# F4_Fc_Board.net
KiCad netlist of a schematic drawn in Altium Designer
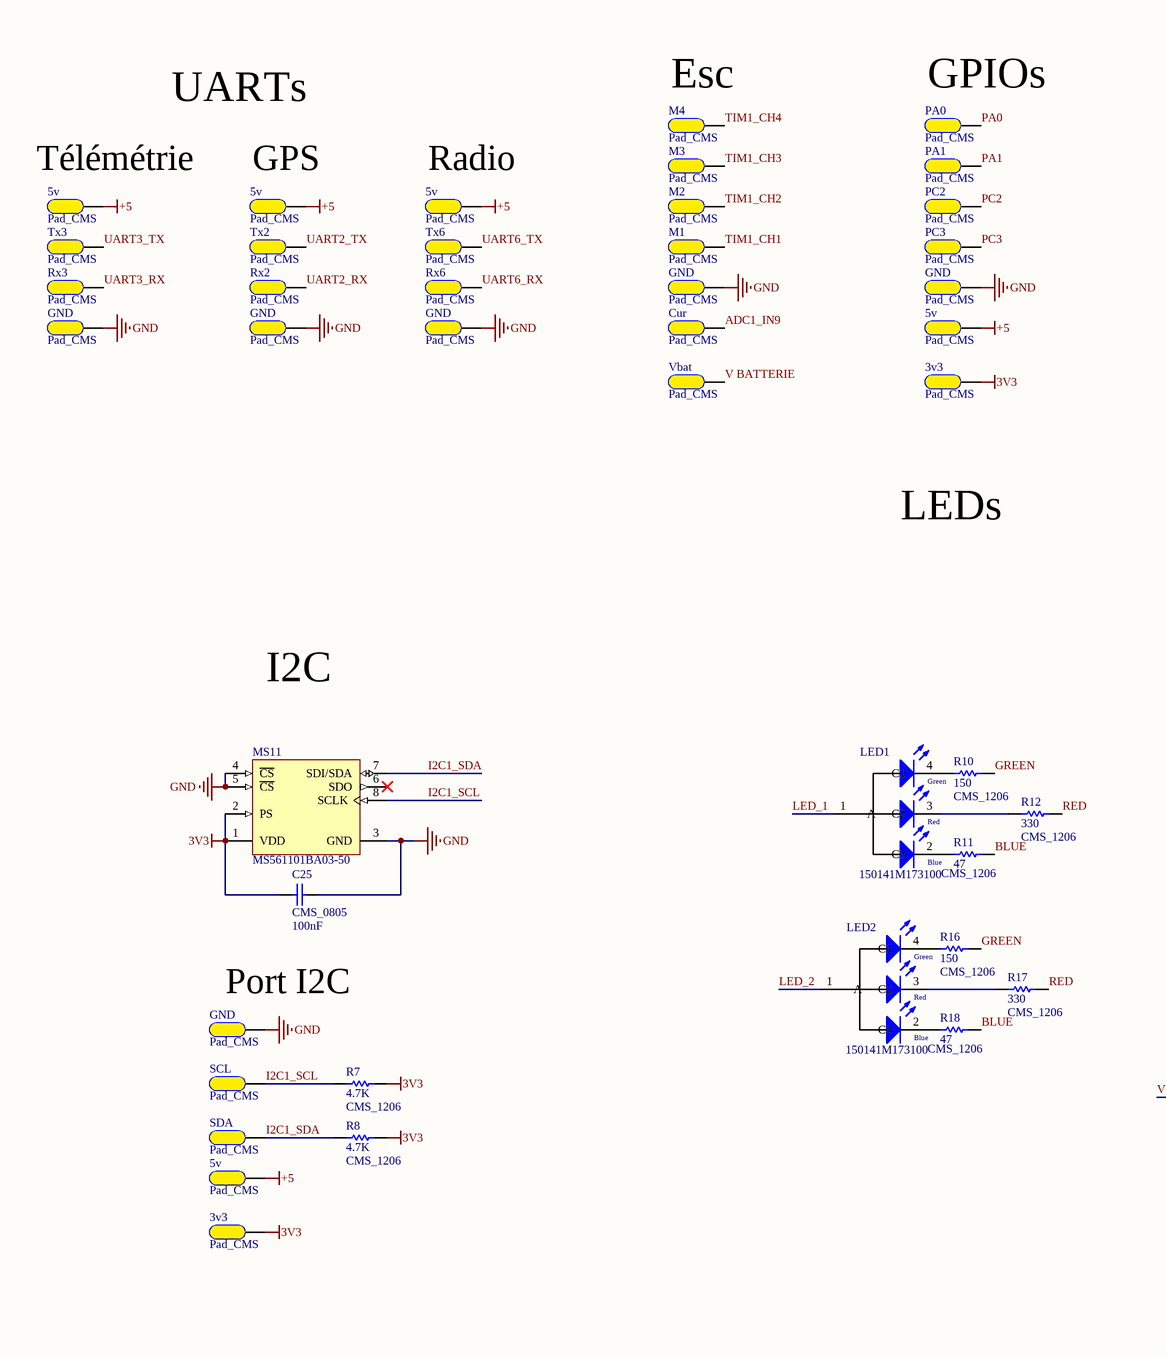
[diagram p0: F4_Fc_Board.SchDoc, left]
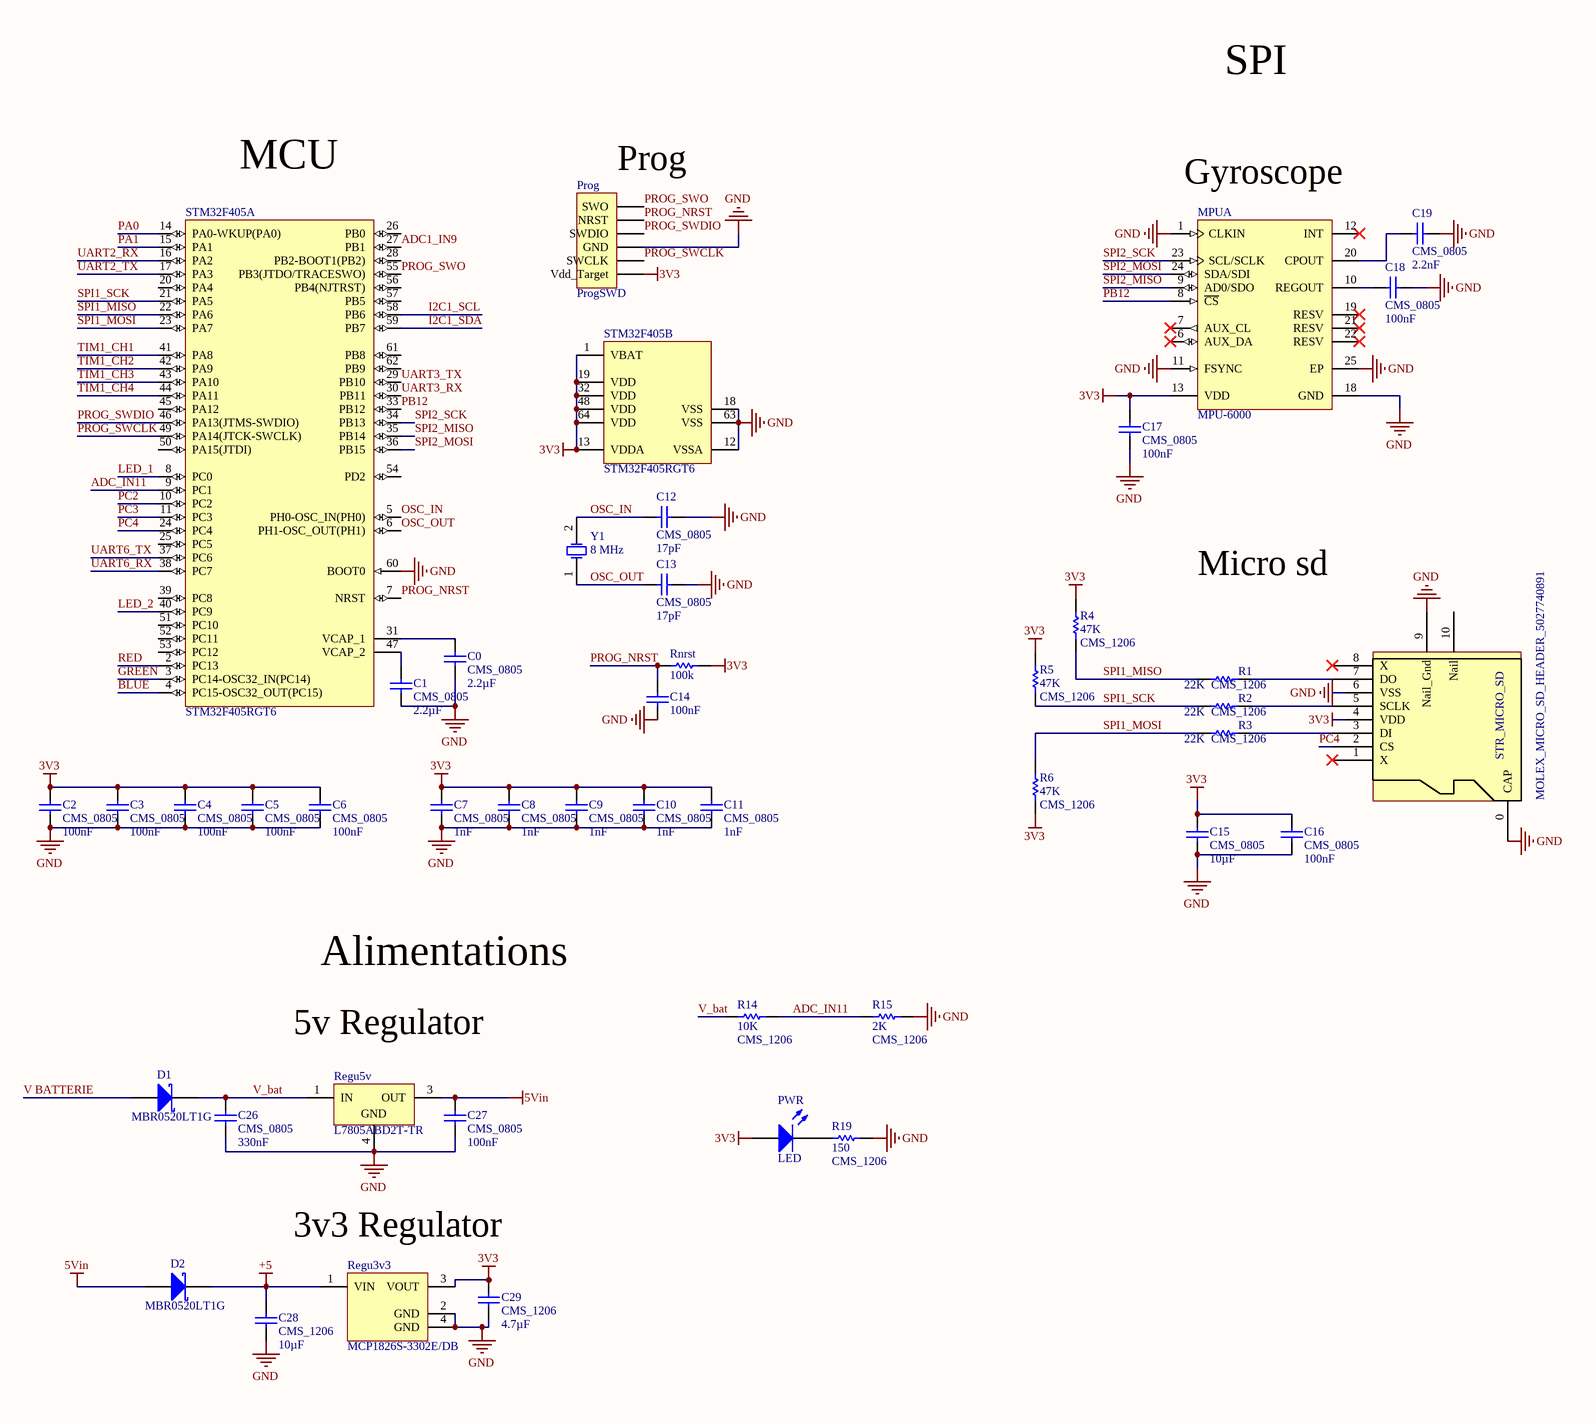
[diagram p1: F4_Fc_Board.SchDoc, right]

(export (version "E")
  (design (tool "Eeschema 10.0.6"))
  (components
    (comp (ref "3v3")
      (value "Pad_CMS")
      (footprint "PAD_CMS_5.08x2.54")
      (description "Pad pour souder un fil")
      (fields (field (name "PUBLISHER") "Damien Guitton"))
      (libsource (lib "Connecteur") (part "Pad_CMS"))
    )
    (comp (ref "5v")
      (value "Pad_CMS")
      (footprint "PAD_CMS_5.08x2.54")
      (description "Pad pour souder un fil")
      (fields (field (name "PUBLISHER") "Damien Guitton"))
      (libsource (lib "Connecteur") (part "Pad_CMS"))
    )
    (comp (ref "C0")
      (value "2.2µF")
      (footprint "CONDENSATEUR_CMS_0805")
      (description "CONDENSATEUR CMS CERAMIQUE 0805")
      (fields (field (name "TYPE") "CMS_0805") (field (name "Comment") "CMS_0805"))
      (libsource (lib "composants passifs") (part "CONDENSATEUR_CMS_CER_0805"))
    )
    (comp (ref "C1")
      (value "2.2µF")
      (footprint "CONDENSATEUR_CMS_0805")
      (description "CONDENSATEUR CMS CERAMIQUE 0805")
      (fields (field (name "TYPE") "CMS_0805") (field (name "Comment") "CMS_0805"))
      (libsource (lib "composants passifs") (part "CONDENSATEUR_CMS_CER_0805"))
    )
    (comp (ref "C2")
      (value "100nF")
      (footprint "CONDENSATEUR_CMS_0805")
      (description "CONDENSATEUR CMS CERAMIQUE 0805")
      (fields (field (name "TYPE") "CMS_0805") (field (name "Comment") "CMS_0805"))
      (libsource (lib "composants passifs") (part "CONDENSATEUR_CMS_CER_0805"))
    )
    (comp (ref "C3")
      (value "100nF")
      (footprint "CONDENSATEUR_CMS_0805")
      (description "CONDENSATEUR CMS CERAMIQUE 0805")
      (fields (field (name "TYPE") "CMS_0805") (field (name "Comment") "CMS_0805"))
      (libsource (lib "composants passifs") (part "CONDENSATEUR_CMS_CER_0805"))
    )
    (comp (ref "C4")
      (value "100nF")
      (footprint "CONDENSATEUR_CMS_0805")
      (description "CONDENSATEUR CMS CERAMIQUE 0805")
      (fields (field (name "TYPE") "CMS_0805") (field (name "Comment") "CMS_0805"))
      (libsource (lib "composants passifs") (part "CONDENSATEUR_CMS_CER_0805"))
    )
    (comp (ref "C5")
      (value "100nF")
      (footprint "CONDENSATEUR_CMS_0805")
      (description "CONDENSATEUR CMS CERAMIQUE 0805")
      (fields (field (name "TYPE") "CMS_0805") (field (name "Comment") "CMS_0805"))
      (libsource (lib "composants passifs") (part "CONDENSATEUR_CMS_CER_0805"))
    )
    (comp (ref "C6")
      (value "100nF")
      (footprint "CONDENSATEUR_CMS_0805")
      (description "CONDENSATEUR CMS CERAMIQUE 0805")
      (fields (field (name "TYPE") "CMS_0805") (field (name "Comment") "CMS_0805"))
      (libsource (lib "composants passifs") (part "CONDENSATEUR_CMS_CER_0805"))
    )
    (comp (ref "C7")
      (value "1nF")
      (footprint "CONDENSATEUR_CMS_0805")
      (description "CONDENSATEUR CMS CERAMIQUE 0805")
      (fields (field (name "TYPE") "CMS_0805") (field (name "Comment") "CMS_0805"))
      (libsource (lib "composants passifs") (part "CONDENSATEUR_CMS_CER_0805"))
    )
    (comp (ref "C8")
      (value "1nF")
      (footprint "CONDENSATEUR_CMS_0805")
      (description "CONDENSATEUR CMS CERAMIQUE 0805")
      (fields (field (name "TYPE") "CMS_0805") (field (name "Comment") "CMS_0805"))
      (libsource (lib "composants passifs") (part "CONDENSATEUR_CMS_CER_0805"))
    )
    (comp (ref "C9")
      (value "1nF")
      (footprint "CONDENSATEUR_CMS_0805")
      (description "CONDENSATEUR CMS CERAMIQUE 0805")
      (fields (field (name "TYPE") "CMS_0805") (field (name "Comment") "CMS_0805"))
      (libsource (lib "composants passifs") (part "CONDENSATEUR_CMS_CER_0805"))
    )
    (comp (ref "C10")
      (value "1nF")
      (footprint "CONDENSATEUR_CMS_0805")
      (description "CONDENSATEUR CMS CERAMIQUE 0805")
      (fields (field (name "TYPE") "CMS_0805") (field (name "Comment") "CMS_0805"))
      (libsource (lib "composants passifs") (part "CONDENSATEUR_CMS_CER_0805"))
    )
    (comp (ref "C11")
      (value "1nF")
      (footprint "CONDENSATEUR_CMS_0805")
      (description "CONDENSATEUR CMS CERAMIQUE 0805")
      (fields (field (name "TYPE") "CMS_0805") (field (name "Comment") "CMS_0805"))
      (libsource (lib "composants passifs") (part "CONDENSATEUR_CMS_CER_0805"))
    )
    (comp (ref "C12")
      (value "17pF")
      (footprint "CONDENSATEUR_CMS_0805")
      (description "CONDENSATEUR CMS CERAMIQUE 0805")
      (fields (field (name "TYPE") "CMS_0805") (field (name "Comment") "CMS_0805"))
      (libsource (lib "composants passifs") (part "CONDENSATEUR_CMS_CER_0805"))
    )
    (comp (ref "C13")
      (value "17pF")
      (footprint "CONDENSATEUR_CMS_0805")
      (description "CONDENSATEUR CMS CERAMIQUE 0805")
      (fields (field (name "TYPE") "CMS_0805") (field (name "Comment") "CMS_0805"))
      (libsource (lib "composants passifs") (part "CONDENSATEUR_CMS_CER_0805"))
    )
    (comp (ref "C14")
      (value "100nF")
      (footprint "C0805_N")
      (description "Capacitor")
      (fields (field (name "PUBLISHER") "Altium Limited"))
      (libsource (lib "_ROBOT") (part "Condensateur"))
    )
    (comp (ref "C15")
      (value "10µF")
      (footprint "CONDENSATEUR_CMS_0805")
      (description "CONDENSATEUR CMS CERAMIQUE 0805")
      (fields (field (name "TYPE") "CMS_0805") (field (name "Comment") "CMS_0805"))
      (libsource (lib "composants passifs") (part "CONDENSATEUR_CMS_CER_0805"))
    )
    (comp (ref "C16")
      (value "100nF")
      (footprint "CONDENSATEUR_CMS_0805")
      (description "CONDENSATEUR CMS CERAMIQUE 0805")
      (fields (field (name "TYPE") "CMS_0805") (field (name "Comment") "CMS_0805"))
      (libsource (lib "composants passifs") (part "CONDENSATEUR_CMS_CER_0805"))
    )
    (comp (ref "C17")
      (value "100nF")
      (footprint "CONDENSATEUR_CMS_0805")
      (description "CONDENSATEUR CMS CERAMIQUE 0805")
      (fields (field (name "TYPE") "CMS_0805") (field (name "Comment") "CMS_0805"))
      (libsource (lib "composants passifs") (part "CONDENSATEUR_CMS_CER_0805"))
    )
    (comp (ref "C18")
      (value "100nF")
      (footprint "CONDENSATEUR_CMS_0805")
      (description "CONDENSATEUR CMS CERAMIQUE 0805")
      (fields (field (name "TYPE") "CMS_0805") (field (name "Comment") "CMS_0805"))
      (libsource (lib "composants passifs") (part "CONDENSATEUR_CMS_CER_0805"))
    )
    (comp (ref "C19")
      (value "2.2nF")
      (footprint "CONDENSATEUR_CMS_0805")
      (description "CONDENSATEUR CMS CERAMIQUE 0805")
      (fields (field (name "TYPE") "CMS_0805") (field (name "Comment") "CMS_0805"))
      (libsource (lib "composants passifs") (part "CONDENSATEUR_CMS_CER_0805"))
    )
    (comp (ref "C25")
      (value "100nF")
      (footprint "CONDENSATEUR_CMS_0805")
      (description "CONDENSATEUR CMS CERAMIQUE 0805")
      (fields (field (name "TYPE") "CMS_0805") (field (name "Comment") "CMS_0805"))
      (libsource (lib "composants passifs") (part "CONDENSATEUR_CMS_CER_0805"))
    )
    (comp (ref "C26")
      (value "330nF")
      (footprint "CONDENSATEUR_CMS_0805")
      (description "CONDENSATEUR CMS CERAMIQUE 0805")
      (fields (field (name "TYPE") "CMS_0805") (field (name "Comment") "CMS_0805"))
      (libsource (lib "composants passifs") (part "CONDENSATEUR_CMS_CER_0805"))
    )
    (comp (ref "C27")
      (value "100nF")
      (footprint "CONDENSATEUR_CMS_0805")
      (description "CONDENSATEUR CMS CERAMIQUE 0805")
      (fields (field (name "TYPE") "CMS_0805") (field (name "Comment") "CMS_0805"))
      (libsource (lib "composants passifs") (part "CONDENSATEUR_CMS_CER_0805"))
    )
    (comp (ref "C28")
      (value "10µF")
      (footprint "CONDENSATEUR_CMS_1206")
      (description "CONDENSATEUR CMS CERAMIQUE 1206")
      (fields (field (name "TYPE") "CMS_1206") (field (name "Comment") "CMS_1206"))
      (libsource (lib "composants passifs") (part "CONDENSATEUR_CMS_CER_1206"))
    )
    (comp (ref "C29")
      (value "4.7µF")
      (footprint "CONDENSATEUR_CMS_1206")
      (description "CONDENSATEUR CMS CERAMIQUE 1206")
      (fields (field (name "TYPE") "CMS_1206") (field (name "Comment") "CMS_1206"))
      (libsource (lib "composants passifs") (part "CONDENSATEUR_CMS_CER_1206"))
    )
    (comp (ref "Cur")
      (value "Pad_CMS")
      (footprint "PAD_CMS_5.08x2.54")
      (description "Pad pour souder un fil")
      (fields (field (name "PUBLISHER") "Damien Guitton"))
      (libsource (lib "Connecteur") (part "Pad_CMS"))
    )
    (comp (ref "D1")
      (value "MBR0520LT1G")
      (footprint "ONSC-SOD-123-2-425-04_V")
      (description "Schottky Power Rectifier, 20 V, 5.5 A, -65 to 125 degC, 2-Pin SMD, RoHS, Tape and Reel")
      (fields (field (name "MANUFACTURER") "ON Semiconductor"))
      (libsource (lib "ESEO (Ecole Supérieure d'Electronique de l'Ouest)") (part "DSKY-AK-2"))
    )
    (comp (ref "D2")
      (value "MBR0520LT1G")
      (footprint "ONSC-SOD-123-2-425-04_V")
      (description "Schottky Power Rectifier, 20 V, 5.5 A, -65 to 125 degC, 2-Pin SMD, RoHS, Tape and Reel")
      (fields (field (name "MANUFACTURER") "ON Semiconductor"))
      (libsource (lib "ESEO (Ecole Supérieure d'Electronique de l'Ouest)") (part "DSKY-AK-2"))
    )
    (comp (ref "GND")
      (value "Pad_CMS")
      (footprint "PAD_CMS_5.08x2.54")
      (description "Pad pour souder un fil")
      (fields (field (name "PUBLISHER") "Damien Guitton"))
      (libsource (lib "Connecteur") (part "Pad_CMS"))
    )
    (comp (ref "LED1")
      (value "150141M173100")
      (footprint "3528_A")
      (description "SMD Full-Color Top LED, WL-SFTW, Red & Green & Blue")
      (fields (field (name "MANUFACTURER") "Wuerth Elektronik"))
      (libsource (lib "Altium Content Vault") (part "WE-LED_RGB_A1B2R3G4-4"))
    )
    (comp (ref "LED2")
      (value "150141M173100")
      (footprint "3528_A")
      (description "SMD Full-Color Top LED, WL-SFTW, Red & Green & Blue")
      (fields (field (name "MANUFACTURER") "Wuerth Elektronik"))
      (libsource (lib "Altium Content Vault") (part "WE-LED_RGB_A1B2R3G4-4"))
    )
    (comp (ref "M1")
      (value "Pad_CMS")
      (footprint "PAD_CMS_5.08x2.54")
      (description "Pad pour souder un fil")
      (fields (field (name "PUBLISHER") "Damien Guitton"))
      (libsource (lib "Connecteur") (part "Pad_CMS"))
    )
    (comp (ref "M2")
      (value "Pad_CMS")
      (footprint "PAD_CMS_5.08x2.54")
      (description "Pad pour souder un fil")
      (fields (field (name "PUBLISHER") "Damien Guitton"))
      (libsource (lib "Connecteur") (part "Pad_CMS"))
    )
    (comp (ref "M3")
      (value "Pad_CMS")
      (footprint "PAD_CMS_5.08x2.54")
      (description "Pad pour souder un fil")
      (fields (field (name "PUBLISHER") "Damien Guitton"))
      (libsource (lib "Connecteur") (part "Pad_CMS"))
    )
    (comp (ref "M4")
      (value "Pad_CMS")
      (footprint "PAD_CMS_5.08x2.54")
      (description "Pad pour souder un fil")
      (fields (field (name "PUBLISHER") "Damien Guitton"))
      (libsource (lib "Connecteur") (part "Pad_CMS"))
    )
    (comp (ref "MPU")
      (value "MPU-6000")
      (footprint "INSE-QFN-24_V")
      (fields (field (name "MANUFACTURER") "InvenSense"))
      (libsource (lib "Altium Content Vault") (part "INSE-MPU-6000"))
    )
    (comp (ref "MS11")
      (value "MS561101BA03-50")
      (footprint "MSI-MS561101BA03-50-8_V")
      (fields (field (name "MANUFACTURER") "Measurement Specialties"))
      (libsource (lib "Altium Content Vault") (part "MSI-MS561101BA03-50-8"))
    )
    (comp (ref "PA0")
      (value "Pad_CMS")
      (footprint "PAD_CMS_5.08x2.54")
      (description "Pad pour souder un fil")
      (fields (field (name "PUBLISHER") "Damien Guitton"))
      (libsource (lib "Connecteur") (part "Pad_CMS"))
    )
    (comp (ref "PA1")
      (value "Pad_CMS")
      (footprint "PAD_CMS_5.08x2.54")
      (description "Pad pour souder un fil")
      (fields (field (name "PUBLISHER") "Damien Guitton"))
      (libsource (lib "Connecteur") (part "Pad_CMS"))
    )
    (comp (ref "PC2")
      (value "Pad_CMS")
      (footprint "PAD_CMS_5.08x2.54")
      (description "Pad pour souder un fil")
      (fields (field (name "PUBLISHER") "Damien Guitton"))
      (libsource (lib "Connecteur") (part "Pad_CMS"))
    )
    (comp (ref "PC3")
      (value "Pad_CMS")
      (footprint "PAD_CMS_5.08x2.54")
      (description "Pad pour souder un fil")
      (fields (field (name "PUBLISHER") "Damien Guitton"))
      (libsource (lib "Connecteur") (part "Pad_CMS"))
    )
    (comp (ref "Prog")
      (value "ProgSWD")
      (footprint "HDR1X6")
      (description "Header, 6-Pin")
      (fields (field (name "PUBLISHER") "Altium Limited"))
      (libsource (lib "DG_Connecteur") (part "Header 6"))
    )
    (comp (ref "PWR")
      (value "LED")
      (footprint "LED_1206")
      (description "Typical LED")
      (fields (field (name "PUBLISHER") "Altium Limited"))
      (libsource (lib "_ROBOT") (part "LED"))
    )
    (comp (ref "R1")
      (value "22K")
      (footprint "RESISTANCE_CMS_1206")
      (description "RESISTANCE CMS 1206")
      (fields (field (name "TYPE") "CMS_1206") (field (name "Comment") "RESISTANCE_CMS_1206"))
      (libsource (lib "composants passifs") (part "RESISTANCE_CMS_1206"))
    )
    (comp (ref "R2")
      (value "22K")
      (footprint "RESISTANCE_CMS_1206")
      (description "RESISTANCE CMS 1206")
      (fields (field (name "TYPE") "CMS_1206") (field (name "Comment") "RESISTANCE_CMS_1206"))
      (libsource (lib "composants passifs") (part "RESISTANCE_CMS_1206"))
    )
    (comp (ref "R3")
      (value "22K")
      (footprint "RESISTANCE_CMS_1206")
      (description "RESISTANCE CMS 1206")
      (fields (field (name "TYPE") "CMS_1206") (field (name "Comment") "RESISTANCE_CMS_1206"))
      (libsource (lib "composants passifs") (part "RESISTANCE_CMS_1206"))
    )
    (comp (ref "R4")
      (value "47K")
      (footprint "RESISTANCE_CMS_1206")
      (description "RESISTANCE CMS 1206")
      (fields (field (name "TYPE") "CMS_1206") (field (name "Comment") "RESISTANCE_CMS_1206"))
      (libsource (lib "composants passifs") (part "RESISTANCE_CMS_1206"))
    )
    (comp (ref "R5")
      (value "47K")
      (footprint "RESISTANCE_CMS_1206")
      (description "RESISTANCE CMS 1206")
      (fields (field (name "TYPE") "CMS_1206") (field (name "Comment") "RESISTANCE_CMS_1206"))
      (libsource (lib "composants passifs") (part "RESISTANCE_CMS_1206"))
    )
    (comp (ref "R6")
      (value "47K")
      (footprint "RESISTANCE_CMS_1206")
      (description "RESISTANCE CMS 1206")
      (fields (field (name "TYPE") "CMS_1206") (field (name "Comment") "RESISTANCE_CMS_1206"))
      (libsource (lib "composants passifs") (part "RESISTANCE_CMS_1206"))
    )
    (comp (ref "R7")
      (value "4.7K")
      (footprint "RESISTANCE_CMS_1206")
      (description "RESISTANCE CMS 1206")
      (fields (field (name "TYPE") "CMS_1206") (field (name "Comment") "RESISTANCE_CMS_1206"))
      (libsource (lib "composants passifs") (part "RESISTANCE_CMS_1206"))
    )
    (comp (ref "R8")
      (value "4.7K")
      (footprint "RESISTANCE_CMS_1206")
      (description "RESISTANCE CMS 1206")
      (fields (field (name "TYPE") "CMS_1206") (field (name "Comment") "RESISTANCE_CMS_1206"))
      (libsource (lib "composants passifs") (part "RESISTANCE_CMS_1206"))
    )
    (comp (ref "R10")
      (value "150")
      (footprint "RESISTANCE_CMS_1206")
      (description "RESISTANCE CMS 1206")
      (fields (field (name "TYPE") "CMS_1206") (field (name "Comment") "RESISTANCE_CMS_1206"))
      (libsource (lib "composants passifs") (part "RESISTANCE_CMS_1206"))
    )
    (comp (ref "R11")
      (value "47")
      (footprint "RESISTANCE_CMS_1206")
      (description "RESISTANCE CMS 1206")
      (fields (field (name "TYPE") "CMS_1206") (field (name "Comment") "RESISTANCE_CMS_1206"))
      (libsource (lib "composants passifs") (part "RESISTANCE_CMS_1206"))
    )
    (comp (ref "R12")
      (value "330")
      (footprint "RESISTANCE_CMS_1206")
      (description "RESISTANCE CMS 1206")
      (fields (field (name "TYPE") "CMS_1206") (field (name "Comment") "RESISTANCE_CMS_1206"))
      (libsource (lib "composants passifs") (part "RESISTANCE_CMS_1206"))
    )
    (comp (ref "R14")
      (value "10K")
      (footprint "RESISTANCE_CMS_1206")
      (description "RESISTANCE CMS 1206")
      (fields (field (name "TYPE") "CMS_1206") (field (name "Comment") "RESISTANCE_CMS_1206"))
      (libsource (lib "composants passifs") (part "RESISTANCE_CMS_1206"))
    )
    (comp (ref "R15")
      (value "2K")
      (footprint "RESISTANCE_CMS_1206")
      (description "RESISTANCE CMS 1206")
      (fields (field (name "TYPE") "CMS_1206") (field (name "Comment") "RESISTANCE_CMS_1206"))
      (libsource (lib "composants passifs") (part "RESISTANCE_CMS_1206"))
    )
    (comp (ref "R16")
      (value "150")
      (footprint "RESISTANCE_CMS_1206")
      (description "RESISTANCE CMS 1206")
      (fields (field (name "TYPE") "CMS_1206") (field (name "Comment") "RESISTANCE_CMS_1206"))
      (libsource (lib "composants passifs") (part "RESISTANCE_CMS_1206"))
    )
    (comp (ref "R17")
      (value "330")
      (footprint "RESISTANCE_CMS_1206")
      (description "RESISTANCE CMS 1206")
      (fields (field (name "TYPE") "CMS_1206") (field (name "Comment") "RESISTANCE_CMS_1206"))
      (libsource (lib "composants passifs") (part "RESISTANCE_CMS_1206"))
    )
    (comp (ref "R18")
      (value "47")
      (footprint "RESISTANCE_CMS_1206")
      (description "RESISTANCE CMS 1206")
      (fields (field (name "TYPE") "CMS_1206") (field (name "Comment") "RESISTANCE_CMS_1206"))
      (libsource (lib "composants passifs") (part "RESISTANCE_CMS_1206"))
    )
    (comp (ref "R19")
      (value "150")
      (footprint "RESISTANCE_CMS_1206")
      (description "RESISTANCE CMS 1206")
      (fields (field (name "TYPE") "CMS_1206") (field (name "Comment") "RESISTANCE_CMS_1206"))
      (libsource (lib "composants passifs") (part "RESISTANCE_CMS_1206"))
    )
    (comp (ref "Regu3v3")
      (value "MCP1826S-3302E/DB")
      (footprint "SOT-223-DB3_L")
      (description "1000 mA, Low Voltage, Low Quiescent Current LDO Regulator, 3-Pin SOT-223, Extended Temperature")
      (libsource (lib "Altium Content Vault") (part "PM-LINEREG-MCP1826-IL4"))
    )
    (comp (ref "Regu5v")
      (value "L7805ABD2T-TR")
      (footprint "TO-263_M")
      (description "Positive Voltage Regulator, 3-Pin D2PAK, Tape and Reel")
      (libsource (lib "Altium Content Vault") (part "PM-REG-L4940-SOT3"))
    )
    (comp (ref "Rnrst")
      (value "100k")
      (footprint "R1206_N")
      (description "Resistor")
      (fields (field (name "PUBLISHER") "Altium Limited"))
      (libsource (lib "_ROBOT") (part "Resistor"))
    )
    (comp (ref "Rx2")
      (value "Pad_CMS")
      (footprint "PAD_CMS_5.08x2.54")
      (description "Pad pour souder un fil")
      (fields (field (name "PUBLISHER") "Damien Guitton"))
      (libsource (lib "Connecteur") (part "Pad_CMS"))
    )
    (comp (ref "Rx3")
      (value "Pad_CMS")
      (footprint "PAD_CMS_5.08x2.54")
      (description "Pad pour souder un fil")
      (fields (field (name "PUBLISHER") "Damien Guitton"))
      (libsource (lib "Connecteur") (part "Pad_CMS"))
    )
    (comp (ref "Rx6")
      (value "Pad_CMS")
      (footprint "PAD_CMS_5.08x2.54")
      (description "Pad pour souder un fil")
      (fields (field (name "PUBLISHER") "Damien Guitton"))
      (libsource (lib "Connecteur") (part "Pad_CMS"))
    )
    (comp (ref "SCL")
      (value "Pad_CMS")
      (footprint "PAD_CMS_5.08x2.54")
      (description "Pad pour souder un fil")
      (fields (field (name "PUBLISHER") "Damien Guitton"))
      (libsource (lib "Connecteur") (part "Pad_CMS"))
    )
    (comp (ref "SDA")
      (value "Pad_CMS")
      (footprint "PAD_CMS_5.08x2.54")
      (description "Pad pour souder un fil")
      (fields (field (name "PUBLISHER") "Damien Guitton"))
      (libsource (lib "Connecteur") (part "Pad_CMS"))
    )
    (comp (ref "STM32F405")
      (value "STM32F405RGT6")
      (footprint "STM-LQFP64_N")
      (fields (field (name "MANUFACTURER") "STMicroelectronics"))
      (libsource (lib "STMicroelectronics STM32 F4") (part "STM32F405RGT6"))
    )
    (comp (ref "STR_MICRO_SD")
      (value "MOLEX_MICRO_SD_HEADER_5027740891")
      (footprint "MOLEX_MICRO_SD_HEADER_5027740891")
      (libsource (lib "Connecteur") (part "MOLEX_MICRO_SD_HEADER_5027740891"))
    )
    (comp (ref "Tx2")
      (value "Pad_CMS")
      (footprint "PAD_CMS_5.08x2.54")
      (description "Pad pour souder un fil")
      (fields (field (name "PUBLISHER") "Damien Guitton"))
      (libsource (lib "Connecteur") (part "Pad_CMS"))
    )
    (comp (ref "Tx3")
      (value "Pad_CMS")
      (footprint "PAD_CMS_5.08x2.54")
      (description "Pad pour souder un fil")
      (fields (field (name "PUBLISHER") "Damien Guitton"))
      (libsource (lib "Connecteur") (part "Pad_CMS"))
    )
    (comp (ref "Tx6")
      (value "Pad_CMS")
      (footprint "PAD_CMS_5.08x2.54")
      (description "Pad pour souder un fil")
      (fields (field (name "PUBLISHER") "Damien Guitton"))
      (libsource (lib "Connecteur") (part "Pad_CMS"))
    )
    (comp (ref "Vbat")
      (value "Pad_CMS")
      (footprint "PAD_CMS_5.08x2.54")
      (description "Pad pour souder un fil")
      (fields (field (name "PUBLISHER") "Damien Guitton"))
      (libsource (lib "Connecteur") (part "Pad_CMS"))
    )
    (comp (ref "Y1")
      (value "8 MHz")
      (footprint "HC49/4H_SMX")
      (description "Crystal Oscillator")
      (fields (field (name "PUBLISHER") "Altium Limited"))
      (libsource (lib "_ROBOT") (part "Quartz"))
    )
  )
  (nets
    (net (code "1") (name "+5") (class "Default")
      (node (ref "5v") (pin "1") (pinfunction "1_1") (pintype "passive"))
      (node (ref "C28") (pin "2") (pinfunction "2_2") (pintype "passive"))
      (node (ref "D2") (pin "2") (pinfunction "K_2") (pintype "passive"))
      (node (ref "Regu3v3") (pin "1") (pinfunction "VIN_1") (pintype "power_in"))
    )
    (net (code "2") (name "/ADC1_IN9") (class "Default")
      (node (ref "Cur") (pin "1") (pinfunction "1_1") (pintype "passive"))
      (node (ref "STM32F405") (pin "27") (pinfunction "PB1_27") (pintype "bidirectional"))
    )
    (net (code "3") (name "/ADC_IN11") (class "Default")
      (node (ref "R14") (pin "2") (pinfunction "2_2") (pintype "passive"))
      (node (ref "R15") (pin "1") (pinfunction "1_1") (pintype "passive"))
      (node (ref "STM32F405") (pin "9") (pinfunction "PC1_9") (pintype "bidirectional"))
    )
    (net (code "4") (name "/BLUE") (class "Default")
      (node (ref "R11") (pin "2") (pinfunction "2_2") (pintype "passive"))
      (node (ref "R18") (pin "2") (pinfunction "2_2") (pintype "passive"))
      (node (ref "STM32F405") (pin "4") (pinfunction "PC15-OSC32_OUT(PC15)_4") (pintype "bidirectional"))
    )
    (net (code "5") (name "/GREEN") (class "Default")
      (node (ref "R10") (pin "2") (pinfunction "2_2") (pintype "passive"))
      (node (ref "R16") (pin "2") (pinfunction "2_2") (pintype "passive"))
      (node (ref "STM32F405") (pin "3") (pinfunction "PC14-OSC32_IN(PC14)_3") (pintype "bidirectional"))
    )
    (net (code "6") (name "/I2C1_SCL") (class "Default")
      (node (ref "MS11") (pin "8") (pinfunction "SCLK_8") (pintype "input"))
      (node (ref "R7") (pin "1") (pinfunction "1_1") (pintype "passive"))
      (node (ref "SCL") (pin "1") (pinfunction "1_1") (pintype "passive"))
      (node (ref "STM32F405") (pin "58") (pinfunction "PB6_58") (pintype "bidirectional"))
    )
    (net (code "7") (name "/I2C1_SDA") (class "Default")
      (node (ref "MS11") (pin "7") (pinfunction "SDI/SDA_7") (pintype "bidirectional"))
      (node (ref "R8") (pin "1") (pinfunction "1_1") (pintype "passive"))
      (node (ref "SDA") (pin "1") (pinfunction "1_1") (pintype "passive"))
      (node (ref "STM32F405") (pin "59") (pinfunction "PB7_59") (pintype "bidirectional"))
    )
    (net (code "8") (name "/LED_1") (class "Default")
      (node (ref "LED1") (pin "1") (pinfunction "A_1") (pintype "passive"))
      (node (ref "STM32F405") (pin "8") (pinfunction "PC0_8") (pintype "bidirectional"))
    )
    (net (code "9") (name "/LED_2") (class "Default")
      (node (ref "LED2") (pin "1") (pinfunction "A_1") (pintype "passive"))
      (node (ref "STM32F405") (pin "40") (pinfunction "PC9_40") (pintype "bidirectional"))
    )
    (net (code "10") (name "/OSC_IN") (class "Default")
      (node (ref "C12") (pin "1") (pinfunction "1_1") (pintype "passive"))
      (node (ref "STM32F405") (pin "5") (pinfunction "PH0-OSC_IN(PH0)_5") (pintype "bidirectional"))
      (node (ref "Y1") (pin "2") (pinfunction "OSC2_2") (pintype "passive"))
    )
    (net (code "11") (name "/OSC_OUT") (class "Default")
      (node (ref "C13") (pin "1") (pinfunction "1_1") (pintype "passive"))
      (node (ref "STM32F405") (pin "6") (pinfunction "PH1-OSC_OUT(PH1)_6") (pintype "bidirectional"))
      (node (ref "Y1") (pin "1") (pinfunction "OSC1_1") (pintype "passive"))
    )
    (net (code "12") (name "/PA0") (class "Default")
      (node (ref "PA0") (pin "1") (pinfunction "1_1") (pintype "passive"))
      (node (ref "STM32F405") (pin "14") (pinfunction "PA0-WKUP(PA0)_14") (pintype "bidirectional"))
    )
    (net (code "13") (name "/PA1") (class "Default")
      (node (ref "PA1") (pin "1") (pinfunction "1_1") (pintype "passive"))
      (node (ref "STM32F405") (pin "15") (pinfunction "PA1_15") (pintype "bidirectional"))
    )
    (net (code "14") (name "/PB12") (class "Default")
      (node (ref "MPU") (pin "8") (pinfunction "~{CS}_8") (pintype "input"))
      (node (ref "STM32F405") (pin "33") (pinfunction "PB12_33") (pintype "bidirectional"))
    )
    (net (code "15") (name "/PC2") (class "Default")
      (node (ref "PC2") (pin "1") (pinfunction "1_1") (pintype "passive"))
      (node (ref "STM32F405") (pin "10") (pinfunction "PC2_10") (pintype "bidirectional"))
    )
    (net (code "16") (name "/PC3") (class "Default")
      (node (ref "PC3") (pin "1") (pinfunction "1_1") (pintype "passive"))
      (node (ref "STM32F405") (pin "11") (pinfunction "PC3_11") (pintype "bidirectional"))
    )
    (net (code "17") (name "/PC4") (class "Default")
      (node (ref "STM32F405") (pin "24") (pinfunction "PC4_24") (pintype "bidirectional"))
      (node (ref "STR_MICRO_SD") (pin "2") (pinfunction "CS_2") (pintype "passive"))
    )
    (net (code "18") (name "/PROG_NRST") (class "Default")
      (node (ref "C14") (pin "2") (pinfunction "2_2") (pintype "passive"))
      (node (ref "Prog") (pin "5") (pinfunction "NRST_5") (pintype "passive"))
      (node (ref "Rnrst") (pin "1") (pinfunction "1_1") (pintype "passive"))
      (node (ref "STM32F405") (pin "7") (pinfunction "NRST_7") (pintype "bidirectional"))
    )
    (net (code "19") (name "/PROG_SWCLK") (class "Default")
      (node (ref "Prog") (pin "2") (pinfunction "SWCLK_2") (pintype "passive"))
      (node (ref "STM32F405") (pin "49") (pinfunction "PA14(JTCK-SWCLK)_49") (pintype "bidirectional"))
    )
    (net (code "20") (name "/PROG_SWDIO") (class "Default")
      (node (ref "Prog") (pin "4") (pinfunction "SWDIO_4") (pintype "passive"))
      (node (ref "STM32F405") (pin "46") (pinfunction "PA13(JTMS-SWDIO)_46") (pintype "bidirectional"))
    )
    (net (code "21") (name "/PROG_SWO") (class "Default")
      (node (ref "Prog") (pin "6") (pinfunction "SWO_6") (pintype "passive"))
      (node (ref "STM32F405") (pin "55") (pinfunction "PB3(JTDO/TRACESWO)_55") (pintype "bidirectional"))
    )
    (net (code "22") (name "/RED") (class "Default")
      (node (ref "R12") (pin "2") (pinfunction "2_2") (pintype "passive"))
      (node (ref "R17") (pin "2") (pinfunction "2_2") (pintype "passive"))
      (node (ref "STM32F405") (pin "2") (pinfunction "PC13_2") (pintype "bidirectional"))
    )
    (net (code "23") (name "/SPI1_MISO") (class "Default")
      (node (ref "R1") (pin "1") (pinfunction "1_1") (pintype "passive"))
      (node (ref "R4") (pin "1") (pinfunction "1_1") (pintype "passive"))
      (node (ref "STM32F405") (pin "22") (pinfunction "PA6_22") (pintype "bidirectional"))
    )
    (net (code "24") (name "/SPI1_MOSI") (class "Default")
      (node (ref "R3") (pin "1") (pinfunction "1_1") (pintype "passive"))
      (node (ref "R6") (pin "2") (pinfunction "2_2") (pintype "passive"))
      (node (ref "STM32F405") (pin "23") (pinfunction "PA7_23") (pintype "bidirectional"))
    )
    (net (code "25") (name "/SPI1_SCK") (class "Default")
      (node (ref "R2") (pin "1") (pinfunction "1_1") (pintype "passive"))
      (node (ref "R5") (pin "1") (pinfunction "1_1") (pintype "passive"))
      (node (ref "STM32F405") (pin "21") (pinfunction "PA5_21") (pintype "bidirectional"))
    )
    (net (code "26") (name "/SPI2_MISO") (class "Default")
      (node (ref "MPU") (pin "9") (pinfunction "AD0/SDO_9") (pintype "bidirectional"))
      (node (ref "STM32F405") (pin "35") (pinfunction "PB14_35") (pintype "bidirectional"))
    )
    (net (code "27") (name "/SPI2_MOSI") (class "Default")
      (node (ref "MPU") (pin "24") (pinfunction "SDA/SDI_24") (pintype "bidirectional"))
      (node (ref "STM32F405") (pin "36") (pinfunction "PB15_36") (pintype "bidirectional"))
    )
    (net (code "28") (name "/SPI2_SCK") (class "Default")
      (node (ref "MPU") (pin "23") (pinfunction "SCL/SCLK_23") (pintype "input"))
      (node (ref "STM32F405") (pin "34") (pinfunction "PB13_34") (pintype "bidirectional"))
    )
    (net (code "29") (name "/TIM1_CH1") (class "Default")
      (node (ref "M1") (pin "1") (pinfunction "1_1") (pintype "passive"))
      (node (ref "STM32F405") (pin "41") (pinfunction "PA8_41") (pintype "bidirectional"))
    )
    (net (code "30") (name "/TIM1_CH2") (class "Default")
      (node (ref "M2") (pin "1") (pinfunction "1_1") (pintype "passive"))
      (node (ref "STM32F405") (pin "42") (pinfunction "PA9_42") (pintype "bidirectional"))
    )
    (net (code "31") (name "/TIM1_CH3") (class "Default")
      (node (ref "M3") (pin "1") (pinfunction "1_1") (pintype "passive"))
      (node (ref "STM32F405") (pin "43") (pinfunction "PA10_43") (pintype "bidirectional"))
    )
    (net (code "32") (name "/TIM1_CH4") (class "Default")
      (node (ref "M4") (pin "1") (pinfunction "1_1") (pintype "passive"))
      (node (ref "STM32F405") (pin "44") (pinfunction "PA11_44") (pintype "bidirectional"))
    )
    (net (code "33") (name "/UART2_RX") (class "Default")
      (node (ref "Rx2") (pin "1") (pinfunction "1_1") (pintype "passive"))
      (node (ref "STM32F405") (pin "16") (pinfunction "PA2_16") (pintype "bidirectional"))
    )
    (net (code "34") (name "/UART2_TX") (class "Default")
      (node (ref "STM32F405") (pin "17") (pinfunction "PA3_17") (pintype "bidirectional"))
      (node (ref "Tx2") (pin "1") (pinfunction "1_1") (pintype "passive"))
    )
    (net (code "35") (name "/UART3_RX") (class "Default")
      (node (ref "Rx3") (pin "1") (pinfunction "1_1") (pintype "passive"))
      (node (ref "STM32F405") (pin "30") (pinfunction "PB11_30") (pintype "bidirectional"))
    )
    (net (code "36") (name "/UART3_TX") (class "Default")
      (node (ref "STM32F405") (pin "29") (pinfunction "PB10_29") (pintype "bidirectional"))
      (node (ref "Tx3") (pin "1") (pinfunction "1_1") (pintype "passive"))
    )
    (net (code "37") (name "/UART6_RX") (class "Default")
      (node (ref "Rx6") (pin "1") (pinfunction "1_1") (pintype "passive"))
      (node (ref "STM32F405") (pin "38") (pinfunction "PC7_38") (pintype "bidirectional"))
    )
    (net (code "38") (name "/UART6_TX") (class "Default")
      (node (ref "STM32F405") (pin "37") (pinfunction "PC6_37") (pintype "bidirectional"))
      (node (ref "Tx6") (pin "1") (pinfunction "1_1") (pintype "passive"))
    )
    (net (code "39") (name "/V BATTERIE") (class "Default")
      (node (ref "D1") (pin "1") (pinfunction "A_1") (pintype "passive"))
      (node (ref "Vbat") (pin "1") (pinfunction "1_1") (pintype "passive"))
    )
    (net (code "40") (name "/V_bat") (class "Default")
      (node (ref "C26") (pin "1") (pinfunction "1_1") (pintype "passive"))
      (node (ref "D1") (pin "2") (pinfunction "K_2") (pintype "passive"))
      (node (ref "R14") (pin "1") (pinfunction "1_1") (pintype "passive"))
      (node (ref "Regu5v") (pin "1") (pinfunction "IN_1") (pintype "power_in"))
    )
    (net (code "41") (name "3V3") (class "Default")
      (node (ref "3v3") (pin "1") (pinfunction "1_1") (pintype "passive"))
      (node (ref "C10") (pin "1") (pinfunction "1_1") (pintype "passive"))
      (node (ref "C11") (pin "1") (pinfunction "1_1") (pintype "passive"))
      (node (ref "C15") (pin "1") (pinfunction "1_1") (pintype "passive"))
      (node (ref "C16") (pin "1") (pinfunction "1_1") (pintype "passive"))
      (node (ref "C17") (pin "2") (pinfunction "2_2") (pintype "passive"))
      (node (ref "C2") (pin "1") (pinfunction "1_1") (pintype "passive"))
      (node (ref "C25") (pin "2") (pinfunction "2_2") (pintype "passive"))
      (node (ref "C29") (pin "2") (pinfunction "2_2") (pintype "passive"))
      (node (ref "C3") (pin "1") (pinfunction "1_1") (pintype "passive"))
      (node (ref "C4") (pin "1") (pinfunction "1_1") (pintype "passive"))
      (node (ref "C5") (pin "1") (pinfunction "1_1") (pintype "passive"))
      (node (ref "C6") (pin "1") (pinfunction "1_1") (pintype "passive"))
      (node (ref "C7") (pin "1") (pinfunction "1_1") (pintype "passive"))
      (node (ref "C8") (pin "1") (pinfunction "1_1") (pintype "passive"))
      (node (ref "C9") (pin "1") (pinfunction "1_1") (pintype "passive"))
      (node (ref "MPU") (pin "13") (pinfunction "VDD_13") (pintype "power_in"))
      (node (ref "MS11") (pin "1") (pinfunction "VDD_1") (pintype "power_in"))
      (node (ref "MS11") (pin "2") (pinfunction "PS_2") (pintype "input"))
      (node (ref "PWR") (pin "1") (pinfunction "A_1") (pintype "passive"))
      (node (ref "Prog") (pin "1") (pinfunction "Vdd_Target_1") (pintype "passive"))
      (node (ref "R4") (pin "2") (pinfunction "2_2") (pintype "passive"))
      (node (ref "R5") (pin "2") (pinfunction "2_2") (pintype "passive"))
      (node (ref "R6") (pin "1") (pinfunction "1_1") (pintype "passive"))
      (node (ref "R7") (pin "2") (pinfunction "2_2") (pintype "passive"))
      (node (ref "R8") (pin "2") (pinfunction "2_2") (pintype "passive"))
      (node (ref "Regu3v3") (pin "3") (pinfunction "VOUT_3") (pintype "power_in"))
      (node (ref "Rnrst") (pin "2") (pinfunction "2_2") (pintype "passive"))
      (node (ref "STM32F405") (pin "1") (pinfunction "VBAT_1") (pintype "power_in"))
      (node (ref "STM32F405") (pin "13") (pinfunction "VDDA_13") (pintype "power_in"))
      (node (ref "STM32F405") (pin "19") (pinfunction "VDD_19") (pintype "power_in"))
      (node (ref "STM32F405") (pin "32") (pinfunction "VDD_32") (pintype "power_in"))
      (node (ref "STM32F405") (pin "48") (pinfunction "VDD_48") (pintype "power_in"))
      (node (ref "STM32F405") (pin "64") (pinfunction "VDD_64") (pintype "power_in"))
      (node (ref "STR_MICRO_SD") (pin "4") (pinfunction "VDD_4") (pintype "passive"))
    )
    (net (code "42") (name "5Vin") (class "Default")
      (node (ref "C27") (pin "1") (pinfunction "1_1") (pintype "passive"))
      (node (ref "D2") (pin "1") (pinfunction "A_1") (pintype "passive"))
      (node (ref "Regu5v") (pin "3") (pinfunction "OUT_3") (pintype "power_in"))
    )
    (net (code "43") (name "GND") (class "Default")
      (node (ref "C0") (pin "2") (pinfunction "2_2") (pintype "passive"))
      (node (ref "C1") (pin "2") (pinfunction "2_2") (pintype "passive"))
      (node (ref "C10") (pin "2") (pinfunction "2_2") (pintype "passive"))
      (node (ref "C11") (pin "2") (pinfunction "2_2") (pintype "passive"))
      (node (ref "C12") (pin "2") (pinfunction "2_2") (pintype "passive"))
      (node (ref "C13") (pin "2") (pinfunction "2_2") (pintype "passive"))
      (node (ref "C14") (pin "1") (pinfunction "1_1") (pintype "passive"))
      (node (ref "C15") (pin "2") (pinfunction "2_2") (pintype "passive"))
      (node (ref "C16") (pin "2") (pinfunction "2_2") (pintype "passive"))
      (node (ref "C17") (pin "1") (pinfunction "1_1") (pintype "passive"))
      (node (ref "C18") (pin "1") (pinfunction "1_1") (pintype "passive"))
      (node (ref "C19") (pin "1") (pinfunction "1_1") (pintype "passive"))
      (node (ref "C2") (pin "2") (pinfunction "2_2") (pintype "passive"))
      (node (ref "C25") (pin "1") (pinfunction "1_1") (pintype "passive"))
      (node (ref "C26") (pin "2") (pinfunction "2_2") (pintype "passive"))
      (node (ref "C27") (pin "2") (pinfunction "2_2") (pintype "passive"))
      (node (ref "C28") (pin "1") (pinfunction "1_1") (pintype "passive"))
      (node (ref "C29") (pin "1") (pinfunction "1_1") (pintype "passive"))
      (node (ref "C3") (pin "2") (pinfunction "2_2") (pintype "passive"))
      (node (ref "C4") (pin "2") (pinfunction "2_2") (pintype "passive"))
      (node (ref "C5") (pin "2") (pinfunction "2_2") (pintype "passive"))
      (node (ref "C6") (pin "2") (pinfunction "2_2") (pintype "passive"))
      (node (ref "C7") (pin "2") (pinfunction "2_2") (pintype "passive"))
      (node (ref "C8") (pin "2") (pinfunction "2_2") (pintype "passive"))
      (node (ref "C9") (pin "2") (pinfunction "2_2") (pintype "passive"))
      (node (ref "GND") (pin "1") (pinfunction "1_1") (pintype "passive"))
      (node (ref "MPU") (pin "1") (pinfunction "CLKIN_1") (pintype "input"))
      (node (ref "MPU") (pin "11") (pinfunction "FSYNC_11") (pintype "input"))
      (node (ref "MPU") (pin "18") (pinfunction "GND_18") (pintype "power_in"))
      (node (ref "MPU") (pin "25") (pinfunction "EP_25") (pintype "passive"))
      (node (ref "MS11") (pin "3") (pinfunction "GND_3") (pintype "power_in"))
      (node (ref "MS11") (pin "4") (pinfunction "~{CS}_4") (pintype "input"))
      (node (ref "MS11") (pin "5") (pinfunction "~{CS}_5") (pintype "input"))
      (node (ref "Prog") (pin "3") (pinfunction "GND_3") (pintype "passive"))
      (node (ref "R15") (pin "2") (pinfunction "2_2") (pintype "passive"))
      (node (ref "R19") (pin "2") (pinfunction "2_2") (pintype "passive"))
      (node (ref "Regu3v3") (pin "2") (pinfunction "GND_2") (pintype "power_in"))
      (node (ref "Regu3v3") (pin "4") (pinfunction "GND_4") (pintype "power_in"))
      (node (ref "Regu5v") (pin "4") (pinfunction "GND_4") (pintype "power_in"))
      (node (ref "STM32F405") (pin "12") (pinfunction "VSSA_12") (pintype "power_in"))
      (node (ref "STM32F405") (pin "18") (pinfunction "VSS_18") (pintype "power_in"))
      (node (ref "STM32F405") (pin "60") (pinfunction "BOOT0_60") (pintype "input"))
      (node (ref "STM32F405") (pin "63") (pinfunction "VSS_63") (pintype "power_in"))
      (node (ref "STR_MICRO_SD") (pin "0") (pinfunction "CAP_0") (pintype "passive"))
      (node (ref "STR_MICRO_SD") (pin "6") (pinfunction "VSS_6") (pintype "passive"))
      (node (ref "STR_MICRO_SD") (pin "9") (pinfunction "Nail_Gnd_9") (pintype "passive"))
    )
    (net (code "44") (name "Net-(LED1-C1)") (class "Default")
      (node (ref "LED1") (pin "4") (pinfunction "C1_4") (pintype "passive"))
      (node (ref "R10") (pin "1") (pinfunction "1_1") (pintype "passive"))
    )
    (net (code "45") (name "Net-(LED1-C2)") (class "Default")
      (node (ref "LED1") (pin "3") (pinfunction "C2_3") (pintype "passive"))
      (node (ref "R12") (pin "1") (pinfunction "1_1") (pintype "passive"))
    )
    (net (code "46") (name "Net-(LED1-C3)") (class "Default")
      (node (ref "LED1") (pin "2") (pinfunction "C3_2") (pintype "passive"))
      (node (ref "R11") (pin "1") (pinfunction "1_1") (pintype "passive"))
    )
    (net (code "47") (name "Net-(LED2-C1)") (class "Default")
      (node (ref "LED2") (pin "4") (pinfunction "C1_4") (pintype "passive"))
      (node (ref "R16") (pin "1") (pinfunction "1_1") (pintype "passive"))
    )
    (net (code "48") (name "Net-(LED2-C2)") (class "Default")
      (node (ref "LED2") (pin "3") (pinfunction "C2_3") (pintype "passive"))
      (node (ref "R17") (pin "1") (pinfunction "1_1") (pintype "passive"))
    )
    (net (code "49") (name "Net-(LED2-C3)") (class "Default")
      (node (ref "LED2") (pin "2") (pinfunction "C3_2") (pintype "passive"))
      (node (ref "R18") (pin "1") (pinfunction "1_1") (pintype "passive"))
    )
    (net (code "50") (name "Net-(MPUA-CPOUT)") (class "Default")
      (node (ref "C19") (pin "2") (pinfunction "2_2") (pintype "passive"))
      (node (ref "MPU") (pin "20") (pinfunction "CPOUT_20") (pintype "passive"))
    )
    (net (code "51") (name "Net-(MPUA-REGOUT)") (class "Default")
      (node (ref "C18") (pin "2") (pinfunction "2_2") (pintype "passive"))
      (node (ref "MPU") (pin "10") (pinfunction "REGOUT_10") (pintype "passive"))
    )
    (net (code "52") (name "Net-(PWR-K)") (class "Default")
      (node (ref "PWR") (pin "2") (pinfunction "K_2") (pintype "passive"))
      (node (ref "R19") (pin "1") (pinfunction "1_1") (pintype "passive"))
    )
    (net (code "53") (name "Net-(STM32F405A-VCAP_1)") (class "Default")
      (node (ref "C0") (pin "1") (pinfunction "1_1") (pintype "passive"))
      (node (ref "STM32F405") (pin "31") (pinfunction "VCAP_1_31") (pintype "power_in"))
    )
    (net (code "54") (name "Net-(STM32F405A-VCAP_2)") (class "Default")
      (node (ref "C1") (pin "1") (pinfunction "1_1") (pintype "passive"))
      (node (ref "STM32F405") (pin "47") (pinfunction "VCAP_2_47") (pintype "power_in"))
    )
    (net (code "55") (name "Net-(STR_MICRO_SD-DI)") (class "Default")
      (node (ref "R3") (pin "2") (pinfunction "2_2") (pintype "passive"))
      (node (ref "STR_MICRO_SD") (pin "3") (pinfunction "DI_3") (pintype "passive"))
    )
    (net (code "56") (name "Net-(STR_MICRO_SD-DO)") (class "Default")
      (node (ref "R1") (pin "2") (pinfunction "2_2") (pintype "passive"))
      (node (ref "STR_MICRO_SD") (pin "7") (pinfunction "DO_7") (pintype "passive"))
    )
    (net (code "57") (name "Net-(STR_MICRO_SD-SCLK)") (class "Default")
      (node (ref "R2") (pin "2") (pinfunction "2_2") (pintype "passive"))
      (node (ref "STR_MICRO_SD") (pin "5") (pinfunction "SCLK_5") (pintype "passive"))
    )
    (net (code "58") (name "unconnected-(MPUA-AUX_CL-Pad7)") (class "Default")
      (node (ref "MPU") (pin "7") (pinfunction "AUX_CL_7") (pintype "output+no_connect"))
    )
    (net (code "59") (name "unconnected-(MPUA-AUX_DA-Pad6)") (class "Default")
      (node (ref "MPU") (pin "6") (pinfunction "AUX_DA_6") (pintype "bidirectional+no_connect"))
    )
    (net (code "60") (name "unconnected-(MPUA-INT-Pad12)") (class "Default")
      (node (ref "MPU") (pin "12") (pinfunction "INT_12") (pintype "open_collector+no_connect"))
    )
    (net (code "61") (name "unconnected-(MPUA-RESV-Pad19)") (class "Default")
      (node (ref "MPU") (pin "19") (pinfunction "RESV_19") (pintype "passive+no_connect"))
    )
    (net (code "62") (name "unconnected-(MPUA-RESV-Pad21)") (class "Default")
      (node (ref "MPU") (pin "21") (pinfunction "RESV_21") (pintype "passive+no_connect"))
    )
    (net (code "63") (name "unconnected-(MPUA-RESV-Pad22)") (class "Default")
      (node (ref "MPU") (pin "22") (pinfunction "RESV_22") (pintype "passive+no_connect"))
    )
    (net (code "64") (name "unconnected-(MS11-SDO-Pad6)") (class "Default")
      (node (ref "MS11") (pin "6") (pinfunction "SDO_6") (pintype "output+no_connect"))
    )
    (net (code "65") (name "unconnected-(STM32F405A-PA4-Pad20)") (class "Default")
      (node (ref "STM32F405") (pin "20") (pinfunction "PA4_20") (pintype "bidirectional"))
    )
    (net (code "66") (name "unconnected-(STM32F405A-PA12-Pad45)") (class "Default")
      (node (ref "STM32F405") (pin "45") (pinfunction "PA12_45") (pintype "bidirectional"))
    )
    (net (code "67") (name "unconnected-(STM32F405A-PA15(JTDI)-Pad50)") (class "Default")
      (node (ref "STM32F405") (pin "50") (pinfunction "PA15(JTDI)_50") (pintype "bidirectional"))
    )
    (net (code "68") (name "unconnected-(STM32F405A-PB0-Pad26)") (class "Default")
      (node (ref "STM32F405") (pin "26") (pinfunction "PB0_26") (pintype "bidirectional"))
    )
    (net (code "69") (name "unconnected-(STM32F405A-PB2-BOOT1(PB2)-Pad28)") (class "Default")
      (node (ref "STM32F405") (pin "28") (pinfunction "PB2-BOOT1(PB2)_28") (pintype "bidirectional"))
    )
    (net (code "70") (name "unconnected-(STM32F405A-PB4(NJTRST)-Pad56)") (class "Default")
      (node (ref "STM32F405") (pin "56") (pinfunction "PB4(NJTRST)_56") (pintype "bidirectional"))
    )
    (net (code "71") (name "unconnected-(STM32F405A-PB5-Pad57)") (class "Default")
      (node (ref "STM32F405") (pin "57") (pinfunction "PB5_57") (pintype "bidirectional"))
    )
    (net (code "72") (name "unconnected-(STM32F405A-PB8-Pad61)") (class "Default")
      (node (ref "STM32F405") (pin "61") (pinfunction "PB8_61") (pintype "bidirectional"))
    )
    (net (code "73") (name "unconnected-(STM32F405A-PB9-Pad62)") (class "Default")
      (node (ref "STM32F405") (pin "62") (pinfunction "PB9_62") (pintype "bidirectional"))
    )
    (net (code "74") (name "unconnected-(STM32F405A-PC5-Pad25)") (class "Default")
      (node (ref "STM32F405") (pin "25") (pinfunction "PC5_25") (pintype "bidirectional"))
    )
    (net (code "75") (name "unconnected-(STM32F405A-PC8-Pad39)") (class "Default")
      (node (ref "STM32F405") (pin "39") (pinfunction "PC8_39") (pintype "bidirectional"))
    )
    (net (code "76") (name "unconnected-(STM32F405A-PC10-Pad51)") (class "Default")
      (node (ref "STM32F405") (pin "51") (pinfunction "PC10_51") (pintype "bidirectional"))
    )
    (net (code "77") (name "unconnected-(STM32F405A-PC11-Pad52)") (class "Default")
      (node (ref "STM32F405") (pin "52") (pinfunction "PC11_52") (pintype "bidirectional"))
    )
    (net (code "78") (name "unconnected-(STM32F405A-PC12-Pad53)") (class "Default")
      (node (ref "STM32F405") (pin "53") (pinfunction "PC12_53") (pintype "bidirectional"))
    )
    (net (code "79") (name "unconnected-(STM32F405A-PD2-Pad54)") (class "Default")
      (node (ref "STM32F405") (pin "54") (pinfunction "PD2_54") (pintype "bidirectional"))
    )
    (net (code "80") (name "unconnected-(STR_MICRO_SD-Nail-Pad10)") (class "Default")
      (node (ref "STR_MICRO_SD") (pin "10") (pinfunction "Nail_10") (pintype "passive"))
    )
    (net (code "81") (name "unconnected-(STR_MICRO_SD-X-Pad1)") (class "Default")
      (node (ref "STR_MICRO_SD") (pin "1") (pinfunction "X_1") (pintype "passive+no_connect"))
    )
    (net (code "82") (name "unconnected-(STR_MICRO_SD-X-Pad8)") (class "Default")
      (node (ref "STR_MICRO_SD") (pin "8") (pinfunction "X_8") (pintype "passive+no_connect"))
    )
  )
)
